# 5V_LS.net
KiCad netlist of a schematic drawn in Altium Designer
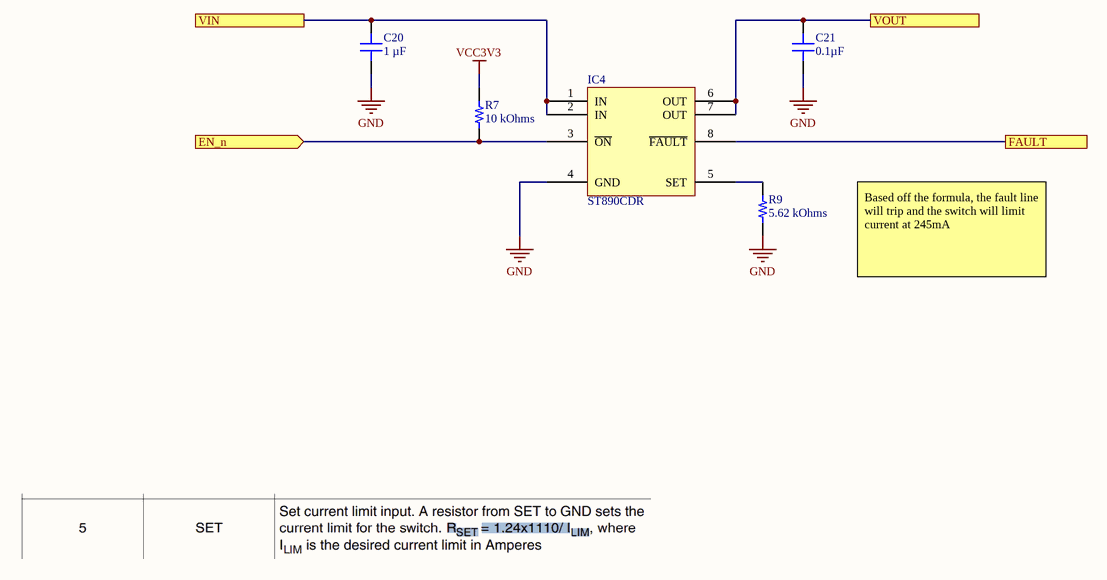
[diagram p0: 5V_LS.SchDoc]

(export (version "E")
  (design (tool "Eeschema 10.0.6"))
  (components
    (comp (ref "C20")
      (value "1 µF")
      (footprint "CAP 0402_1005")
      (description "CAP CER 1UF 10V X7S 0402")
      (fields
        (field (name "PART NUMBER") "GRM155C71A105KE11D")
        (field (name "MANUFACTURER") "Murata Electronics")
      )
      (libsource (lib "Celestial") (part "Capacitor"))
    )
    (comp (ref "C21")
      (value "0.1µF")
      (footprint "CAP 0402_1005")
      (description "CAP CER 0.1UF 10V X7R 0402")
      (fields (field (name "PART NUMBER") "0402ZC104KAT2A") (field (name "MANUFACTURER") "AVX Corporation"))
      (libsource (lib "Celestial") (part "Capacitor"))
    )
    (comp (ref "IC4")
      (value "ST890CDR")
      (footprint "ST SOIC-8N")
      (description "IC PWR SWITCH P-CHANNEL 1:1 8SO")
      (fields (field (name "MANUFACTURER") "STMicroelectronics"))
      (libsource (lib "Celestial") (part "ST ST890CDR"))
    )
    (comp (ref "R7")
      (value "10 kOhms")
      (footprint "RES 0402_1005")
      (description "RES 10K OHM 0.1% 1/10W 0402")
      (fields
        (field (name "PART NUMBER") "RP73PF1E10KBTD")
        (field (name "MANUFACTURER") "TE Connectivity Passive Product")
      )
      (libsource (lib "Celestial") (part "Resistor"))
    )
    (comp (ref "R9")
      (value "5.62 kOhms")
      (footprint "RES 0402_1005")
      (description "RES 5.62K OHM 0.1% 1/10W 0402")
      (fields
        (field (name "PART NUMBER") "RP73PF1E5K62BTD")
        (field (name "MANUFACTURER") "TE Connectivity Passive Product")
      )
      (libsource (lib "Celestial") (part "Resistor"))
    )
  )
  (nets
    (net (code "1") (name "/EN_n") (class "Default")
      (node (ref "IC4") (pin "3") (pinfunction "~{ON}_3") (pintype "passive"))
      (node (ref "R7") (pin "1") (pinfunction "1_1") (pintype "passive"))
    )
    (net (code "2") (name "/FAULT") (class "Default")
      (node (ref "IC4") (pin "8") (pinfunction "~{FAULT}_8") (pintype "passive"))
    )
    (net (code "3") (name "/VIN") (class "Default")
      (node (ref "C20") (pin "2") (pinfunction "2_2") (pintype "passive"))
      (node (ref "IC4") (pin "1") (pinfunction "IN_1") (pintype "passive"))
      (node (ref "IC4") (pin "2") (pinfunction "IN_2") (pintype "passive"))
    )
    (net (code "4") (name "/VOUT") (class "Default")
      (node (ref "C21") (pin "2") (pinfunction "2_2") (pintype "passive"))
      (node (ref "IC4") (pin "6") (pinfunction "OUT_6") (pintype "passive"))
      (node (ref "IC4") (pin "7") (pinfunction "OUT_7") (pintype "passive"))
    )
    (net (code "5") (name "GND") (class "Default")
      (node (ref "C20") (pin "1") (pinfunction "1_1") (pintype "passive"))
      (node (ref "C21") (pin "1") (pinfunction "1_1") (pintype "passive"))
      (node (ref "IC4") (pin "4") (pinfunction "GND_4") (pintype "passive"))
      (node (ref "R9") (pin "1") (pinfunction "1_1") (pintype "passive"))
    )
    (net (code "6") (name "Net-(IC4-SET)") (class "Default")
      (node (ref "IC4") (pin "5") (pinfunction "SET_5") (pintype "passive"))
      (node (ref "R9") (pin "2") (pinfunction "2_2") (pintype "passive"))
    )
    (net (code "7") (name "VCC3V3") (class "Default")
      (node (ref "R7") (pin "2") (pinfunction "2_2") (pintype "passive"))
    )
  )
)
